# V_K.net
KiCad netlist of a schematic drawn in Altium Designer
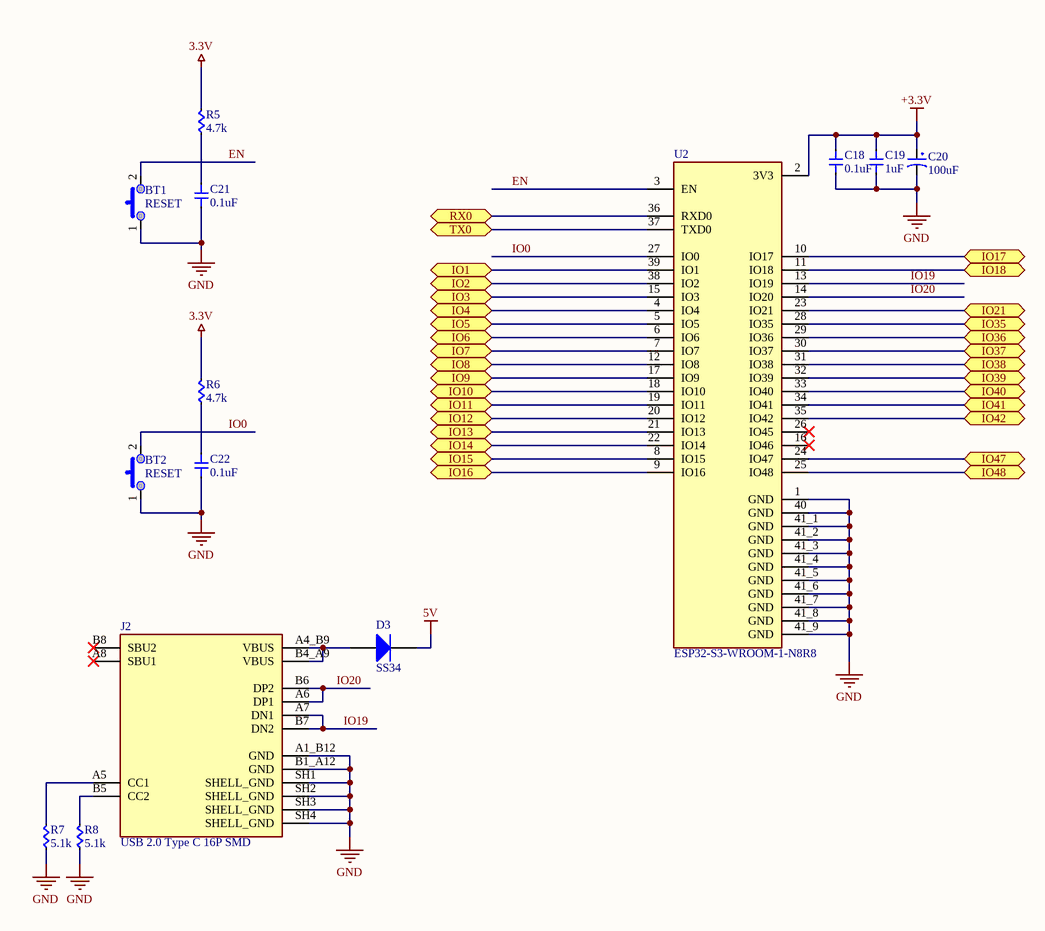
[diagram p0: VĐK.SchDoc]

(export (version "E")
  (design (tool "Eeschema 10.0.6"))
  (components
    (comp (ref "BT1")
      (value "RESET")
      (footprint "B3U-1000P")
      (libsource (lib "Altium_Lib_PTK") (part "Button_2p"))
    )
    (comp (ref "BT2")
      (value "RESET")
      (footprint "B3U-1000P")
      (libsource (lib "Altium_Lib_PTK") (part "Button_2p"))
    )
    (comp (ref "C18")
      (value "0.1uF")
      (footprint "Cap 0603")
      (description "Capacitor SMD 0603")
      (libsource (lib "Altium_Lib_PTK") (part "Cap 0603"))
    )
    (comp (ref "C19")
      (value "1uF")
      (footprint "Cap 0603")
      (description "Capacitor SMD 0603")
      (libsource (lib "Altium_Lib_PTK") (part "Cap 0603"))
    )
    (comp (ref "C20")
      (value "100uF")
      (footprint "tu tantalum smd7343")
      (description "Dán")
      (libsource (lib "Altium_Lib_PTK") (part "Tu tantalum 100uF 25V SMD7343"))
    )
    (comp (ref "C21")
      (value "0.1uF")
      (footprint "Cap 0603")
      (description "Capacitor SMD 0603")
      (libsource (lib "Altium_Lib_PTK") (part "Cap 0603"))
    )
    (comp (ref "C22")
      (value "0.1uF")
      (footprint "Cap 0603")
      (description "Capacitor SMD 0603")
      (libsource (lib "Altium_Lib_PTK") (part "Cap 0603"))
    )
    (comp (ref "D3")
      (value "SS34")
      (footprint "DIODE SMA")
      (description "Dán")
      (libsource (lib "Altium_Lib_PTK") (part "Diode SS34 ( 1N5822 )"))
    )
    (comp (ref "J2")
      (value "USB 2.0 Type C 16P SMD")
      (footprint "TYPE C 16P SMD")
      (fields (field (name "MF") "Global Connector Technology") (field (name "MP") "USB4105GFA120"))
      (libsource (lib "Power PLC") (part "USB 2.0 Type C 16P SMD"))
    )
    (comp (ref "R5")
      (value "4.7k")
      (footprint "RES 0603")
      (description "RES SMD 0603")
      (fields
        (field (name "MANUFACTURER") "Vishay Dale")
        (field (name "MANUFACTURER PART NUMBER") "CRCW040210K0FKED")
      )
      (libsource (lib "Altium_Lib_PTK") (part "RES 0603"))
    )
    (comp (ref "R6")
      (value "4.7k")
      (footprint "RES 0603")
      (description "RES SMD 0603")
      (fields
        (field (name "MANUFACTURER") "Vishay Dale")
        (field (name "MANUFACTURER PART NUMBER") "CRCW040210K0FKED")
      )
      (libsource (lib "Altium_Lib_PTK") (part "RES 0603"))
    )
    (comp (ref "R7")
      (value "5.1k")
      (footprint "RES 0603")
      (description "RES SMD 0603")
      (fields
        (field (name "MANUFACTURER") "Vishay Dale")
        (field (name "MANUFACTURER PART NUMBER") "CRCW040210K0FKED")
      )
      (libsource (lib "Altium_Lib_PTK") (part "RES 0603"))
    )
    (comp (ref "R8")
      (value "5.1k")
      (footprint "RES 0603")
      (description "RES SMD 0603")
      (fields
        (field (name "MANUFACTURER") "Vishay Dale")
        (field (name "MANUFACTURER PART NUMBER") "CRCW040210K0FKED")
      )
      (libsource (lib "Altium_Lib_PTK") (part "RES 0603"))
    )
    (comp (ref "U2")
      (value "ESP32-S3-WROOM-1-N8R8")
      (footprint "XCVR_ESP32S3WROOM1N8R8")
      (description "Bluetooth, WiFi 802.11b/g/n, Bluetooth v5.0 Transceiver Module 2.4GHz PCB Trace Surface Mount")
      (fields (field (name "MF") "Espressif Systems"))
      (libsource (lib "Altium_Lib_PTK") (part "ESP32-S3-WROOM-1-N8R8"))
    )
  )
  (nets
    (net (code "1") (name "+3.3V") (class "Default")
      (node (ref "C18") (pin "1") (pinfunction "1_1") (pintype "passive"))
      (node (ref "C19") (pin "1") (pinfunction "1_1") (pintype "passive"))
      (node (ref "C20") (pin "1") (pinfunction "1_1") (pintype "passive"))
      (node (ref "U2") (pin "2") (pinfunction "3V3_2") (pintype "power_in"))
    )
    (net (code "2") (name "/EN") (class "Default")
      (node (ref "BT1") (pin "2") (pinfunction "2_2") (pintype "passive"))
      (node (ref "U2") (pin "3") (pinfunction "EN_3") (pintype "passive"))
    )
    (net (code "3") (name "/IO0") (class "Default")
      (node (ref "BT2") (pin "2") (pinfunction "2_2") (pintype "passive"))
      (node (ref "U2") (pin "27") (pinfunction "IO0_27") (pintype "passive"))
    )
    (net (code "4") (name "/IO1") (class "Default")
      (node (ref "U2") (pin "39") (pinfunction "IO1_39") (pintype "passive"))
    )
    (net (code "5") (name "/IO2") (class "Default")
      (node (ref "U2") (pin "38") (pinfunction "IO2_38") (pintype "passive"))
    )
    (net (code "6") (name "/IO3") (class "Default")
      (node (ref "U2") (pin "15") (pinfunction "IO3_15") (pintype "passive"))
    )
    (net (code "7") (name "/IO4") (class "Default")
      (node (ref "U2") (pin "4") (pinfunction "IO4_4") (pintype "passive"))
    )
    (net (code "8") (name "/IO5") (class "Default")
      (node (ref "U2") (pin "5") (pinfunction "IO5_5") (pintype "passive"))
    )
    (net (code "9") (name "/IO6") (class "Default")
      (node (ref "U2") (pin "6") (pinfunction "IO6_6") (pintype "passive"))
    )
    (net (code "10") (name "/IO7") (class "Default")
      (node (ref "U2") (pin "7") (pinfunction "IO7_7") (pintype "passive"))
    )
    (net (code "11") (name "/IO8") (class "Default")
      (node (ref "U2") (pin "12") (pinfunction "IO8_12") (pintype "passive"))
    )
    (net (code "12") (name "/IO9") (class "Default")
      (node (ref "U2") (pin "17") (pinfunction "IO9_17") (pintype "passive"))
    )
    (net (code "13") (name "/IO10") (class "Default")
      (node (ref "U2") (pin "18") (pinfunction "IO10_18") (pintype "passive"))
    )
    (net (code "14") (name "/IO11") (class "Default")
      (node (ref "U2") (pin "19") (pinfunction "IO11_19") (pintype "passive"))
    )
    (net (code "15") (name "/IO12") (class "Default")
      (node (ref "U2") (pin "20") (pinfunction "IO12_20") (pintype "passive"))
    )
    (net (code "16") (name "/IO13") (class "Default")
      (node (ref "U2") (pin "21") (pinfunction "IO13_21") (pintype "passive"))
    )
    (net (code "17") (name "/IO14") (class "Default")
      (node (ref "U2") (pin "22") (pinfunction "IO14_22") (pintype "passive"))
    )
    (net (code "18") (name "/IO15") (class "Default")
      (node (ref "U2") (pin "8") (pinfunction "IO15_8") (pintype "passive"))
    )
    (net (code "19") (name "/IO16") (class "Default")
      (node (ref "U2") (pin "9") (pinfunction "IO16_9") (pintype "passive"))
    )
    (net (code "20") (name "/IO17") (class "Default")
      (node (ref "U2") (pin "10") (pinfunction "IO17_10") (pintype "passive"))
    )
    (net (code "21") (name "/IO18") (class "Default")
      (node (ref "U2") (pin "11") (pinfunction "IO18_11") (pintype "passive"))
    )
    (net (code "22") (name "/IO19") (class "Default")
      (node (ref "J2") (pin "A7") (pinfunction "DN1_A7") (pintype "passive"))
      (node (ref "J2") (pin "B7") (pinfunction "DN2_B7") (pintype "passive"))
      (node (ref "U2") (pin "13") (pinfunction "IO19_13") (pintype "passive"))
    )
    (net (code "23") (name "/IO20") (class "Default")
      (node (ref "J2") (pin "A6") (pinfunction "DP1_A6") (pintype "passive"))
      (node (ref "J2") (pin "B6") (pinfunction "DP2_B6") (pintype "passive"))
      (node (ref "U2") (pin "14") (pinfunction "IO20_14") (pintype "passive"))
    )
    (net (code "24") (name "/IO21") (class "Default")
      (node (ref "U2") (pin "23") (pinfunction "IO21_23") (pintype "passive"))
    )
    (net (code "25") (name "/IO35") (class "Default")
      (node (ref "U2") (pin "28") (pinfunction "IO35_28") (pintype "passive"))
    )
    (net (code "26") (name "/IO36") (class "Default")
      (node (ref "U2") (pin "29") (pinfunction "IO36_29") (pintype "passive"))
    )
    (net (code "27") (name "/IO37") (class "Default")
      (node (ref "U2") (pin "30") (pinfunction "IO37_30") (pintype "passive"))
    )
    (net (code "28") (name "/IO38") (class "Default")
      (node (ref "U2") (pin "31") (pinfunction "IO38_31") (pintype "passive"))
    )
    (net (code "29") (name "/IO39") (class "Default")
      (node (ref "U2") (pin "32") (pinfunction "IO39_32") (pintype "passive"))
    )
    (net (code "30") (name "/IO40") (class "Default")
      (node (ref "U2") (pin "33") (pinfunction "IO40_33") (pintype "passive"))
    )
    (net (code "31") (name "/IO41") (class "Default")
      (node (ref "U2") (pin "34") (pinfunction "IO41_34") (pintype "passive"))
    )
    (net (code "32") (name "/IO42") (class "Default")
      (node (ref "U2") (pin "35") (pinfunction "IO42_35") (pintype "passive"))
    )
    (net (code "33") (name "/IO47") (class "Default")
      (node (ref "U2") (pin "24") (pinfunction "IO47_24") (pintype "passive"))
    )
    (net (code "34") (name "/IO48") (class "Default")
      (node (ref "U2") (pin "25") (pinfunction "IO48_25") (pintype "passive"))
    )
    (net (code "35") (name "/RX0") (class "Default")
      (node (ref "U2") (pin "36") (pinfunction "RXD0_36") (pintype "passive"))
    )
    (net (code "36") (name "/TX0") (class "Default")
      (node (ref "U2") (pin "37") (pinfunction "TXD0_37") (pintype "passive"))
    )
    (net (code "37") (name "3.3V") (class "Default")
      (node (ref "R5") (pin "2") (pinfunction "2_2") (pintype "passive"))
      (node (ref "R6") (pin "2") (pinfunction "2_2") (pintype "passive"))
    )
    (net (code "38") (name "5V") (class "Default")
      (node (ref "D3") (pin "2") (pinfunction "K_2") (pintype "passive"))
    )
    (net (code "39") (name "GND") (class "Default")
      (node (ref "BT1") (pin "1") (pinfunction "1_1") (pintype "passive"))
      (node (ref "BT2") (pin "1") (pinfunction "1_1") (pintype "passive"))
      (node (ref "C18") (pin "2") (pinfunction "2_2") (pintype "passive"))
      (node (ref "C19") (pin "2") (pinfunction "2_2") (pintype "passive"))
      (node (ref "C20") (pin "2") (pinfunction "2_2") (pintype "passive"))
      (node (ref "C21") (pin "2") (pinfunction "2_2") (pintype "passive"))
      (node (ref "C22") (pin "2") (pinfunction "2_2") (pintype "passive"))
      (node (ref "J2") (pin "A1_B12") (pinfunction "GND_A1_B12") (pintype "power_in"))
      (node (ref "J2") (pin "B1_A12") (pinfunction "GND_B1_A12") (pintype "power_in"))
      (node (ref "J2") (pin "SH1") (pinfunction "SHELL_GND_SH1") (pintype "power_in"))
      (node (ref "J2") (pin "SH2") (pinfunction "SHELL_GND_SH2") (pintype "power_in"))
      (node (ref "J2") (pin "SH3") (pinfunction "SHELL_GND_SH3") (pintype "power_in"))
      (node (ref "J2") (pin "SH4") (pinfunction "SHELL_GND_SH4") (pintype "power_in"))
      (node (ref "R7") (pin "1") (pinfunction "1_1") (pintype "passive"))
      (node (ref "R8") (pin "1") (pinfunction "1_1") (pintype "passive"))
      (node (ref "U2") (pin "1") (pinfunction "GND_1") (pintype "power_in"))
      (node (ref "U2") (pin "40") (pinfunction "GND_40") (pintype "power_in"))
      (node (ref "U2") (pin "41_1") (pinfunction "GND_41_1") (pintype "power_in"))
      (node (ref "U2") (pin "41_2") (pinfunction "GND_41_2") (pintype "power_in"))
      (node (ref "U2") (pin "41_3") (pinfunction "GND_41_3") (pintype "power_in"))
      (node (ref "U2") (pin "41_4") (pinfunction "GND_41_4") (pintype "power_in"))
      (node (ref "U2") (pin "41_5") (pinfunction "GND_41_5") (pintype "power_in"))
      (node (ref "U2") (pin "41_6") (pinfunction "GND_41_6") (pintype "power_in"))
      (node (ref "U2") (pin "41_7") (pinfunction "GND_41_7") (pintype "power_in"))
      (node (ref "U2") (pin "41_8") (pinfunction "GND_41_8") (pintype "power_in"))
      (node (ref "U2") (pin "41_9") (pinfunction "GND_41_9") (pintype "power_in"))
    )
    (net (code "40") (name "Net-(C21-Pad1)") (class "Default")
      (node (ref "C21") (pin "1") (pinfunction "1_1") (pintype "passive"))
      (node (ref "R5") (pin "1") (pinfunction "1_1") (pintype "passive"))
    )
    (net (code "41") (name "Net-(C22-Pad1)") (class "Default")
      (node (ref "C22") (pin "1") (pinfunction "1_1") (pintype "passive"))
      (node (ref "R6") (pin "1") (pinfunction "1_1") (pintype "passive"))
    )
    (net (code "42") (name "Net-(D3-A)") (class "Default")
      (node (ref "D3") (pin "1") (pinfunction "A_1") (pintype "passive"))
      (node (ref "J2") (pin "A4_B9") (pinfunction "VBUS_A4_B9") (pintype "power_in"))
      (node (ref "J2") (pin "B4_A9") (pinfunction "VBUS_B4_A9") (pintype "power_in"))
    )
    (net (code "43") (name "Net-(J2-CC1)") (class "Default")
      (node (ref "J2") (pin "A5") (pinfunction "CC1_A5") (pintype "passive"))
      (node (ref "R7") (pin "2") (pinfunction "2_2") (pintype "passive"))
    )
    (net (code "44") (name "Net-(J2-CC2)") (class "Default")
      (node (ref "J2") (pin "B5") (pinfunction "CC2_B5") (pintype "passive"))
      (node (ref "R8") (pin "2") (pinfunction "2_2") (pintype "passive"))
    )
    (net (code "45") (name "unconnected-(J2-SBU1-PadA8)") (class "Default")
      (node (ref "J2") (pin "A8") (pinfunction "SBU1_A8") (pintype "passive+no_connect"))
    )
    (net (code "46") (name "unconnected-(J2-SBU2-PadB8)") (class "Default")
      (node (ref "J2") (pin "B8") (pinfunction "SBU2_B8") (pintype "passive+no_connect"))
    )
    (net (code "47") (name "unconnected-(U2-IO45-Pad26)") (class "Default")
      (node (ref "U2") (pin "26") (pinfunction "IO45_26") (pintype "passive+no_connect"))
    )
    (net (code "48") (name "unconnected-(U2-IO46-Pad16)") (class "Default")
      (node (ref "U2") (pin "16") (pinfunction "IO46_16") (pintype "passive+no_connect"))
    )
  )
)
